# fpga-bank0-outside.net
KiCad netlist of a schematic drawn in Altium Designer
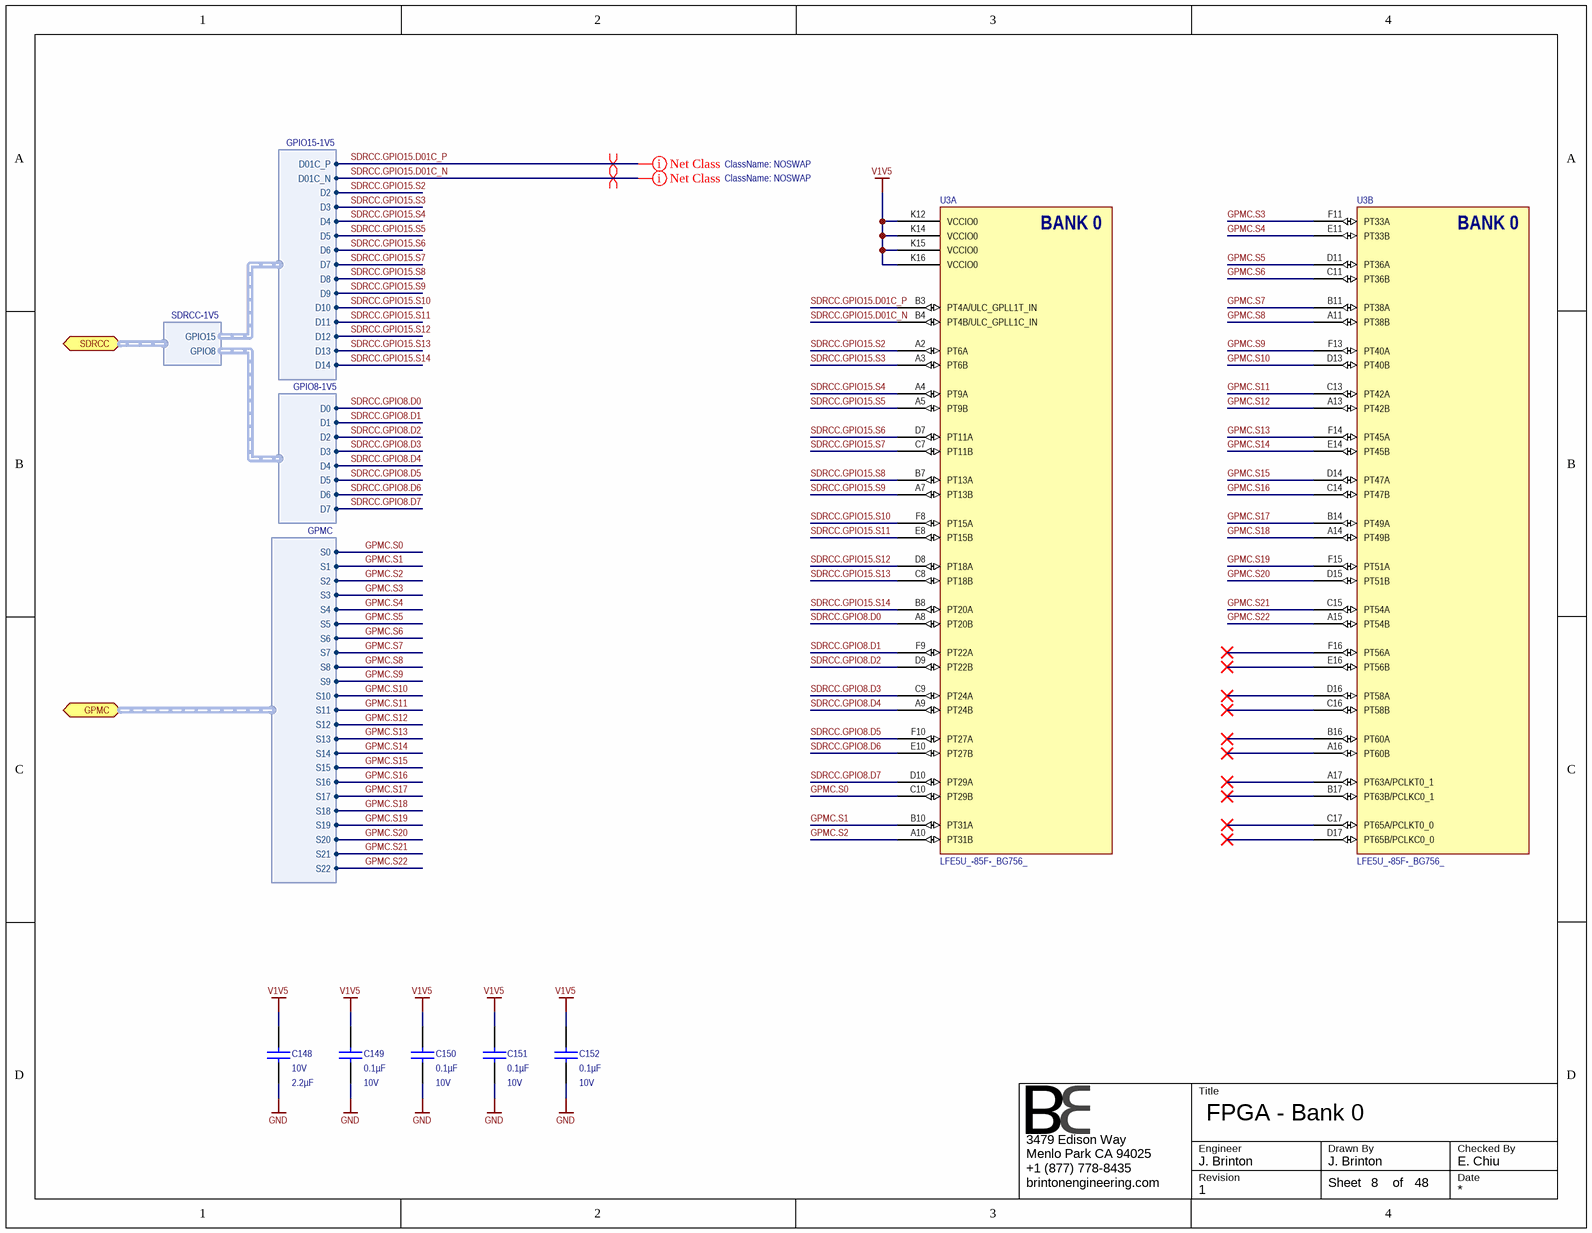
[diagram p0: fpga-bank0-outside.SchDoc]

(export (version "E")
  (design (tool "Eeschema 10.0.6"))
  (components
    (comp (ref "C148")
      (value "GRM188R71A225KE15D")
      (footprint "CAPC1608X90N")
      (description "CAP CER 2.2UF 10V 10% X7R 0603")
      (fields
        (field (name "MANUFACTURER") "Murata Electronics North America")
        (field (name "TOLERANCE") "±10%")
        (field (name "VOLTAGE - RATED") "10V")
        (field (name "CAPACITANCE") "2.2µF")
      )
      (libsource (lib "murata") (part "GRM188R71A225KE15D"))
    )
    (comp (ref "C149")
      (value "GRM155R71A104KA01J")
      (footprint "CAPC1005X56N")
      (description "CAP CER 0.1UF 10V 10% X7R 0402")
      (fields
        (field (name "MANUFACTURER") "Murata Electronics North America")
        (field (name "TOLERANCE") "±10%")
        (field (name "CAPACITANCE") "0.1µF")
        (field (name "VOLTAGE - RATED") "10V")
      )
      (libsource (lib "murata") (part "GRM155R71A104KA01J"))
    )
    (comp (ref "C150")
      (value "GRM155R71A104KA01J")
      (footprint "CAPC1005X56N")
      (description "CAP CER 0.1UF 10V 10% X7R 0402")
      (fields
        (field (name "MANUFACTURER") "Murata Electronics North America")
        (field (name "TOLERANCE") "±10%")
        (field (name "CAPACITANCE") "0.1µF")
        (field (name "VOLTAGE - RATED") "10V")
      )
      (libsource (lib "murata") (part "GRM155R71A104KA01J"))
    )
    (comp (ref "C151")
      (value "GRM155R71A104KA01J")
      (footprint "CAPC1005X56N")
      (description "CAP CER 0.1UF 10V 10% X7R 0402")
      (fields
        (field (name "MANUFACTURER") "Murata Electronics North America")
        (field (name "TOLERANCE") "±10%")
        (field (name "CAPACITANCE") "0.1µF")
        (field (name "VOLTAGE - RATED") "10V")
      )
      (libsource (lib "murata") (part "GRM155R71A104KA01J"))
    )
    (comp (ref "C152")
      (value "GRM155R71A104KA01J")
      (footprint "CAPC1005X56N")
      (description "CAP CER 0.1UF 10V 10% X7R 0402")
      (fields
        (field (name "MANUFACTURER") "Murata Electronics North America")
        (field (name "TOLERANCE") "±10%")
        (field (name "CAPACITANCE") "0.1µF")
        (field (name "VOLTAGE - RATED") "10V")
      )
      (libsource (lib "murata") (part "GRM155R71A104KA01J"))
    )
    (comp (ref "U3")
      (value "LFE5U_-85F-_BG756_")
      (footprint "lattice:caBGA756")
      (description "ECP5 FPGA, 85k LUT, 756-caBGA")
      (fields (field (name "MANUFACTURER") "Lattice Semiconductor"))
      (libsource (lib "lattice") (part "LFE5U_-85F-_BG756_"))
    )
  )
  (nets
    (net (code "4") (name "/GPMC.S0") (class "Default")
      (node (ref "U3") (pin "C10") (pinfunction "PT29B_C10") (pintype "bidirectional"))
    )
    (net (code "5") (name "/GPMC.S1") (class "Default")
      (node (ref "U3") (pin "B10") (pinfunction "PT31A_B10") (pintype "bidirectional"))
    )
    (net (code "6") (name "/GPMC.S2") (class "Default")
      (node (ref "U3") (pin "A10") (pinfunction "PT31B_A10") (pintype "bidirectional"))
    )
    (net (code "7") (name "/GPMC.S3") (class "Default")
      (node (ref "U3") (pin "F11") (pinfunction "PT33A_F11") (pintype "bidirectional"))
    )
    (net (code "8") (name "/GPMC.S4") (class "Default")
      (node (ref "U3") (pin "E11") (pinfunction "PT33B_E11") (pintype "bidirectional"))
    )
    (net (code "9") (name "/GPMC.S5") (class "Default")
      (node (ref "U3") (pin "D11") (pinfunction "PT36A_D11") (pintype "bidirectional"))
    )
    (net (code "10") (name "/GPMC.S6") (class "Default")
      (node (ref "U3") (pin "C11") (pinfunction "PT36B_C11") (pintype "bidirectional"))
    )
    (net (code "11") (name "/GPMC.S7") (class "Default")
      (node (ref "U3") (pin "B11") (pinfunction "PT38A_B11") (pintype "bidirectional"))
    )
    (net (code "12") (name "/GPMC.S8") (class "Default")
      (node (ref "U3") (pin "A11") (pinfunction "PT38B_A11") (pintype "bidirectional"))
    )
    (net (code "13") (name "/GPMC.S9") (class "Default")
      (node (ref "U3") (pin "F13") (pinfunction "PT40A_F13") (pintype "bidirectional"))
    )
    (net (code "14") (name "/GPMC.S10") (class "Default")
      (node (ref "U3") (pin "D13") (pinfunction "PT40B_D13") (pintype "bidirectional"))
    )
    (net (code "15") (name "/GPMC.S11") (class "Default")
      (node (ref "U3") (pin "C13") (pinfunction "PT42A_C13") (pintype "bidirectional"))
    )
    (net (code "16") (name "/GPMC.S12") (class "Default")
      (node (ref "U3") (pin "A13") (pinfunction "PT42B_A13") (pintype "bidirectional"))
    )
    (net (code "17") (name "/GPMC.S13") (class "Default")
      (node (ref "U3") (pin "F14") (pinfunction "PT45A_F14") (pintype "bidirectional"))
    )
    (net (code "18") (name "/GPMC.S14") (class "Default")
      (node (ref "U3") (pin "E14") (pinfunction "PT45B_E14") (pintype "bidirectional"))
    )
    (net (code "19") (name "/GPMC.S15") (class "Default")
      (node (ref "U3") (pin "D14") (pinfunction "PT47A_D14") (pintype "bidirectional"))
    )
    (net (code "20") (name "/GPMC.S16") (class "Default")
      (node (ref "U3") (pin "C14") (pinfunction "PT47B_C14") (pintype "bidirectional"))
    )
    (net (code "21") (name "/GPMC.S17") (class "Default")
      (node (ref "U3") (pin "B14") (pinfunction "PT49A_B14") (pintype "bidirectional"))
    )
    (net (code "22") (name "/GPMC.S18") (class "Default")
      (node (ref "U3") (pin "A14") (pinfunction "PT49B_A14") (pintype "bidirectional"))
    )
    (net (code "23") (name "/GPMC.S19") (class "Default")
      (node (ref "U3") (pin "F15") (pinfunction "PT51A_F15") (pintype "bidirectional"))
    )
    (net (code "24") (name "/GPMC.S20") (class "Default")
      (node (ref "U3") (pin "D15") (pinfunction "PT51B_D15") (pintype "bidirectional"))
    )
    (net (code "25") (name "/GPMC.S21") (class "Default")
      (node (ref "U3") (pin "C15") (pinfunction "PT54A_C15") (pintype "bidirectional"))
    )
    (net (code "26") (name "/GPMC.S22") (class "Default")
      (node (ref "U3") (pin "A15") (pinfunction "PT54B_A15") (pintype "bidirectional"))
    )
    (net (code "27") (name "/SDRCC.GPIO8.D0") (class "Default")
      (node (ref "U3") (pin "A8") (pinfunction "PT20B_A8") (pintype "bidirectional"))
    )
    (net (code "28") (name "/SDRCC.GPIO8.D1") (class "Default")
      (node (ref "U3") (pin "F9") (pinfunction "PT22A_F9") (pintype "bidirectional"))
    )
    (net (code "29") (name "/SDRCC.GPIO8.D2") (class "Default")
      (node (ref "U3") (pin "D9") (pinfunction "PT22B_D9") (pintype "bidirectional"))
    )
    (net (code "30") (name "/SDRCC.GPIO8.D3") (class "Default")
      (node (ref "U3") (pin "C9") (pinfunction "PT24A_C9") (pintype "bidirectional"))
    )
    (net (code "31") (name "/SDRCC.GPIO8.D4") (class "Default")
      (node (ref "U3") (pin "A9") (pinfunction "PT24B_A9") (pintype "bidirectional"))
    )
    (net (code "32") (name "/SDRCC.GPIO8.D5") (class "Default")
      (node (ref "U3") (pin "F10") (pinfunction "PT27A_F10") (pintype "bidirectional"))
    )
    (net (code "33") (name "/SDRCC.GPIO8.D6") (class "Default")
      (node (ref "U3") (pin "E10") (pinfunction "PT27B_E10") (pintype "bidirectional"))
    )
    (net (code "34") (name "/SDRCC.GPIO8.D7") (class "Default")
      (node (ref "U3") (pin "D10") (pinfunction "PT29A_D10") (pintype "bidirectional"))
    )
    (net (code "35") (name "/SDRCC.GPIO15.D01C_N") (class "Default")
      (node (ref "U3") (pin "B4") (pinfunction "PT4B/ULC_GPLL1C_IN_B4") (pintype "bidirectional"))
    )
    (net (code "36") (name "/SDRCC.GPIO15.D01C_P") (class "Default")
      (node (ref "U3") (pin "B3") (pinfunction "PT4A/ULC_GPLL1T_IN_B3") (pintype "bidirectional"))
    )
    (net (code "37") (name "/SDRCC.GPIO15.S2") (class "Default")
      (node (ref "U3") (pin "A2") (pinfunction "PT6A_A2") (pintype "bidirectional"))
    )
    (net (code "38") (name "/SDRCC.GPIO15.S3") (class "Default")
      (node (ref "U3") (pin "A3") (pinfunction "PT6B_A3") (pintype "bidirectional"))
    )
    (net (code "39") (name "/SDRCC.GPIO15.S4") (class "Default")
      (node (ref "U3") (pin "A4") (pinfunction "PT9A_A4") (pintype "bidirectional"))
    )
    (net (code "40") (name "/SDRCC.GPIO15.S5") (class "Default")
      (node (ref "U3") (pin "A5") (pinfunction "PT9B_A5") (pintype "bidirectional"))
    )
    (net (code "41") (name "/SDRCC.GPIO15.S6") (class "Default")
      (node (ref "U3") (pin "D7") (pinfunction "PT11A_D7") (pintype "bidirectional"))
    )
    (net (code "42") (name "/SDRCC.GPIO15.S7") (class "Default")
      (node (ref "U3") (pin "C7") (pinfunction "PT11B_C7") (pintype "bidirectional"))
    )
    (net (code "43") (name "/SDRCC.GPIO15.S8") (class "Default")
      (node (ref "U3") (pin "B7") (pinfunction "PT13A_B7") (pintype "bidirectional"))
    )
    (net (code "44") (name "/SDRCC.GPIO15.S9") (class "Default")
      (node (ref "U3") (pin "A7") (pinfunction "PT13B_A7") (pintype "bidirectional"))
    )
    (net (code "45") (name "/SDRCC.GPIO15.S10") (class "Default")
      (node (ref "U3") (pin "F8") (pinfunction "PT15A_F8") (pintype "bidirectional"))
    )
    (net (code "46") (name "/SDRCC.GPIO15.S11") (class "Default")
      (node (ref "U3") (pin "E8") (pinfunction "PT15B_E8") (pintype "bidirectional"))
    )
    (net (code "47") (name "/SDRCC.GPIO15.S12") (class "Default")
      (node (ref "U3") (pin "D8") (pinfunction "PT18A_D8") (pintype "bidirectional"))
    )
    (net (code "48") (name "/SDRCC.GPIO15.S13") (class "Default")
      (node (ref "U3") (pin "C8") (pinfunction "PT18B_C8") (pintype "bidirectional"))
    )
    (net (code "49") (name "/SDRCC.GPIO15.S14") (class "Default")
      (node (ref "U3") (pin "B8") (pinfunction "PT20A_B8") (pintype "bidirectional"))
    )
    (net (code "53") (name "GND") (class "Default")
      (node (ref "C148") (pin "1") (pinfunction "1_1") (pintype "passive"))
      (node (ref "C149") (pin "1") (pinfunction "1_1") (pintype "passive"))
      (node (ref "C150") (pin "1") (pinfunction "1_1") (pintype "passive"))
      (node (ref "C151") (pin "1") (pinfunction "1_1") (pintype "passive"))
      (node (ref "C152") (pin "1") (pinfunction "1_1") (pintype "passive"))
    )
    (net (code "54") (name "V1V5") (class "Default")
      (node (ref "C148") (pin "2") (pinfunction "2_2") (pintype "passive"))
      (node (ref "C149") (pin "2") (pinfunction "2_2") (pintype "passive"))
      (node (ref "C150") (pin "2") (pinfunction "2_2") (pintype "passive"))
      (node (ref "C151") (pin "2") (pinfunction "2_2") (pintype "passive"))
      (node (ref "C152") (pin "2") (pinfunction "2_2") (pintype "passive"))
      (node (ref "U3") (pin "K12") (pinfunction "VCCIO0_K12") (pintype "power_in"))
      (node (ref "U3") (pin "K14") (pinfunction "VCCIO0_K14") (pintype "power_in"))
      (node (ref "U3") (pin "K15") (pinfunction "VCCIO0_K15") (pintype "power_in"))
      (node (ref "U3") (pin "K16") (pinfunction "VCCIO0_K16") (pintype "power_in"))
    )
    (net (code "55") (name "unconnected-(U3B-PT56A-PadF16)") (class "Default")
      (node (ref "U3") (pin "F16") (pinfunction "PT56A_F16") (pintype "bidirectional+no_connect"))
    )
    (net (code "56") (name "unconnected-(U3B-PT56B-PadE16)") (class "Default")
      (node (ref "U3") (pin "E16") (pinfunction "PT56B_E16") (pintype "bidirectional+no_connect"))
    )
    (net (code "57") (name "unconnected-(U3B-PT58A-PadD16)") (class "Default")
      (node (ref "U3") (pin "D16") (pinfunction "PT58A_D16") (pintype "bidirectional+no_connect"))
    )
    (net (code "58") (name "unconnected-(U3B-PT58B-PadC16)") (class "Default")
      (node (ref "U3") (pin "C16") (pinfunction "PT58B_C16") (pintype "bidirectional+no_connect"))
    )
    (net (code "59") (name "unconnected-(U3B-PT60A-PadB16)") (class "Default")
      (node (ref "U3") (pin "B16") (pinfunction "PT60A_B16") (pintype "bidirectional+no_connect"))
    )
    (net (code "60") (name "unconnected-(U3B-PT60B-PadA16)") (class "Default")
      (node (ref "U3") (pin "A16") (pinfunction "PT60B_A16") (pintype "bidirectional+no_connect"))
    )
    (net (code "61") (name "unconnected-(U3B-PT63A{slash}PCLKT0_1-PadA17)") (class "Default")
      (node (ref "U3") (pin "A17") (pinfunction "PT63A/PCLKT0_1_A17") (pintype "bidirectional+no_connect"))
    )
    (net (code "62") (name "unconnected-(U3B-PT63B{slash}PCLKC0_1-PadB17)") (class "Default")
      (node (ref "U3") (pin "B17") (pinfunction "PT63B/PCLKC0_1_B17") (pintype "bidirectional+no_connect"))
    )
    (net (code "63") (name "unconnected-(U3B-PT65A{slash}PCLKT0_0-PadC17)") (class "Default")
      (node (ref "U3") (pin "C17") (pinfunction "PT65A/PCLKT0_0_C17") (pintype "bidirectional+no_connect"))
    )
    (net (code "64") (name "unconnected-(U3B-PT65B{slash}PCLKC0_0-PadD17)") (class "Default")
      (node (ref "U3") (pin "D17") (pinfunction "PT65B/PCLKC0_0_D17") (pintype "bidirectional+no_connect"))
    )
  )
)
